# InterfacePagamentos.net
KiCad netlist of a schematic drawn in Altium Designer
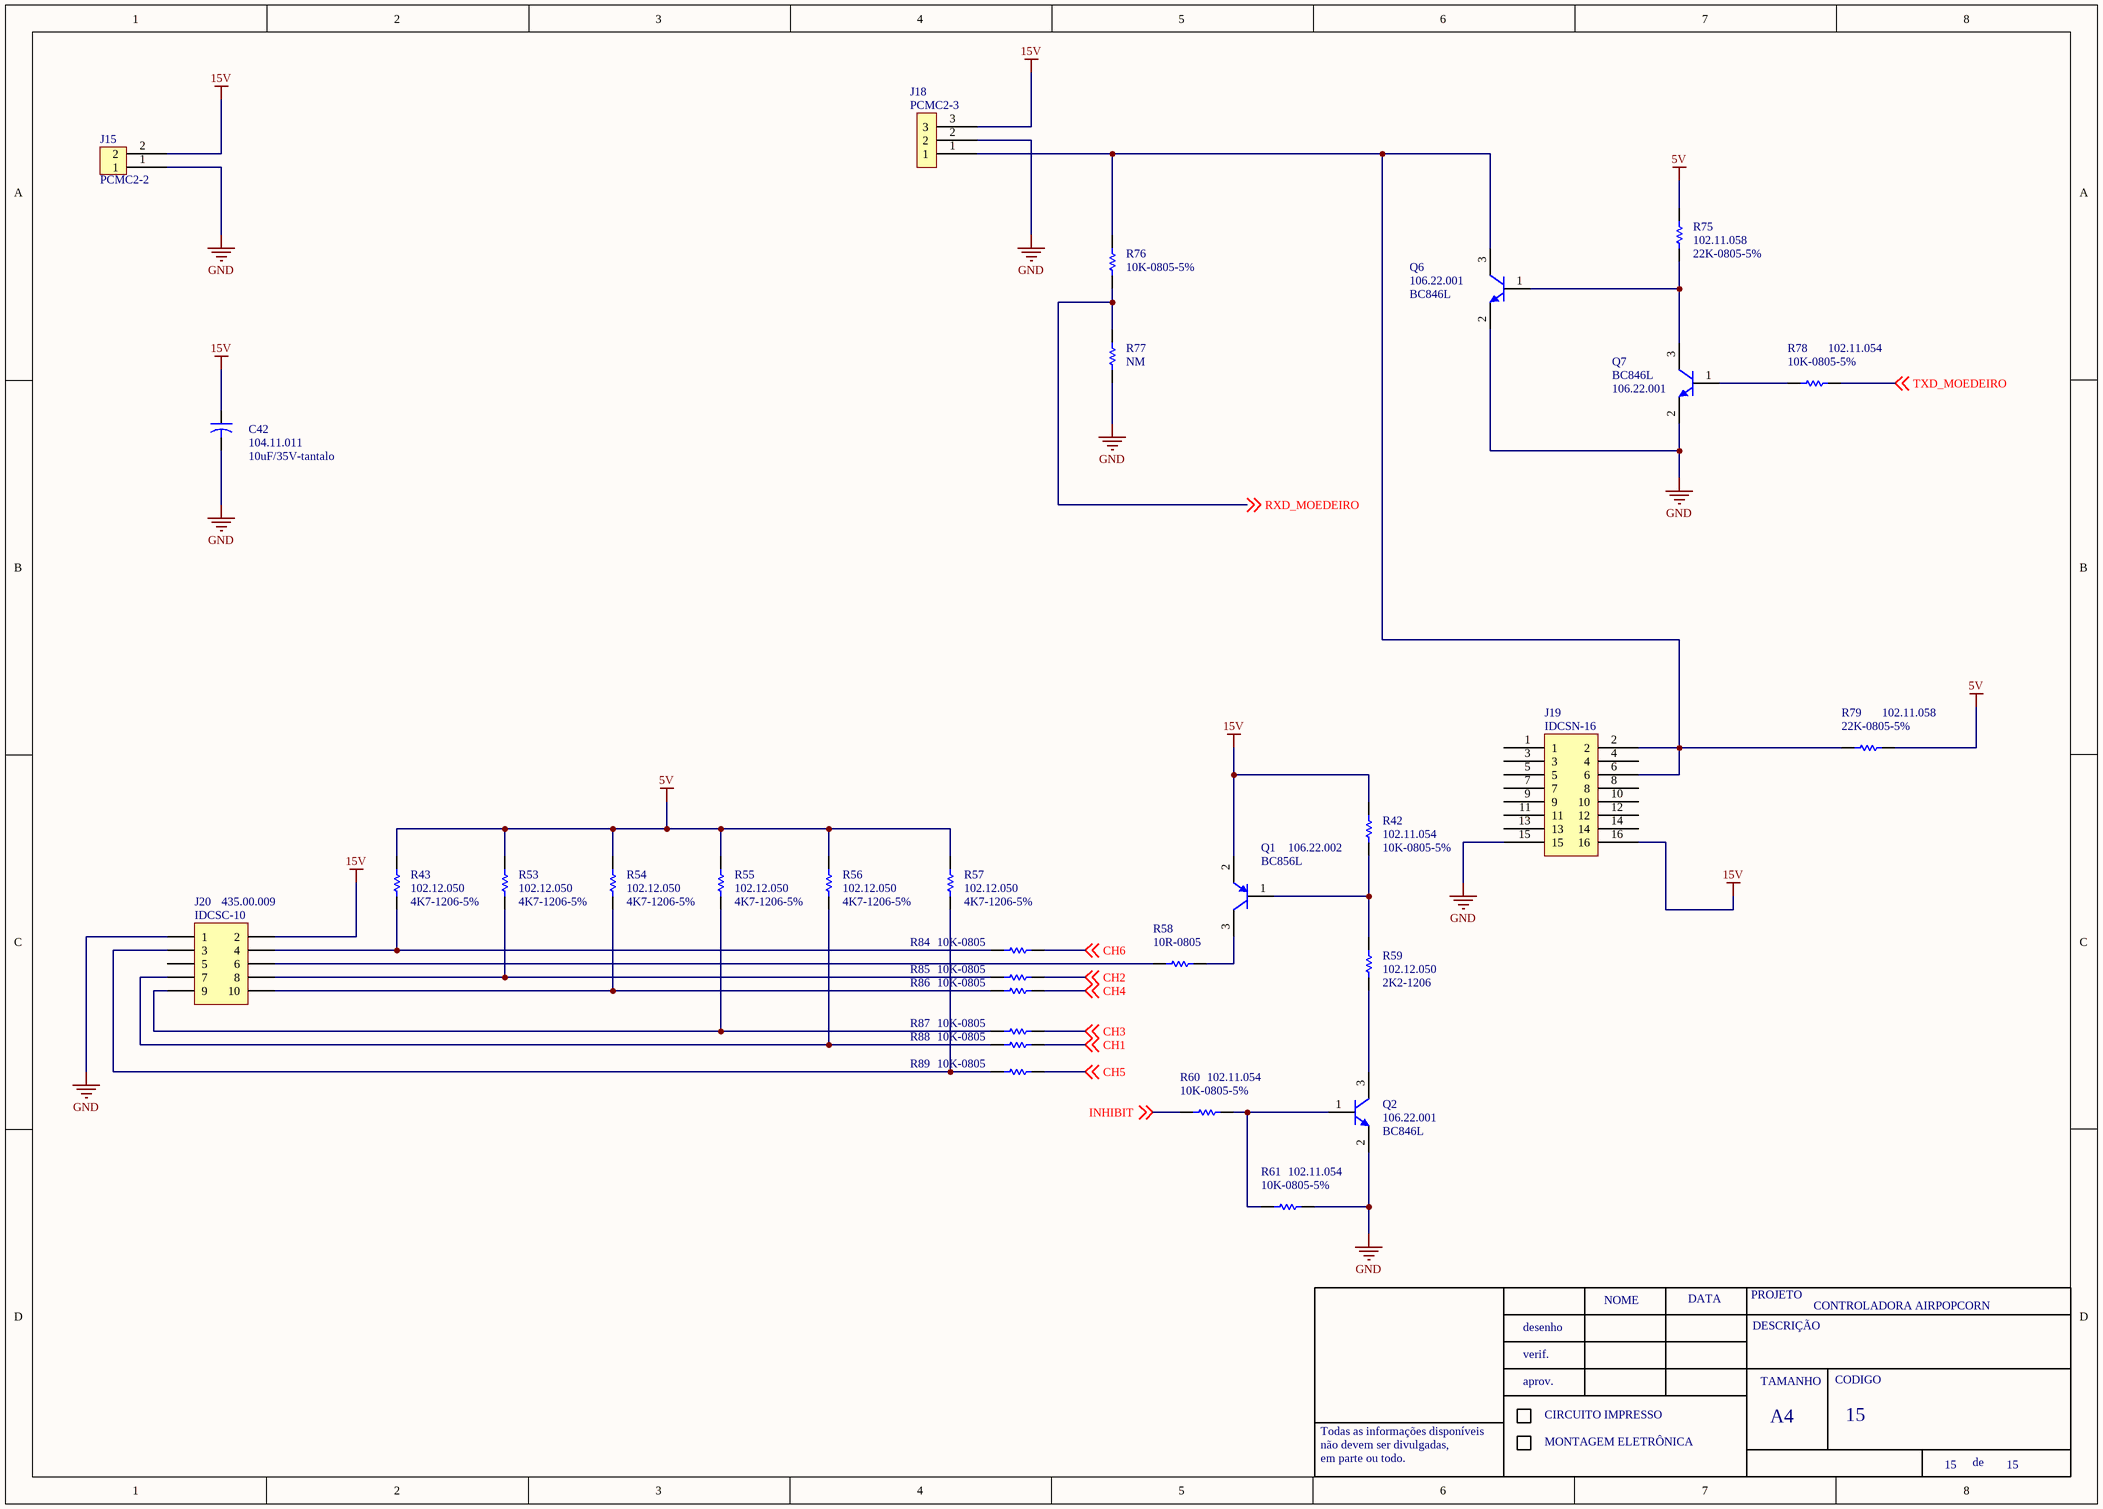
[diagram p0: InterfacePagamentos.SchDoc]

(export (version "E")
  (design (tool "Eeschema 10.0.6"))
  (components
    (comp (ref "C42")
      (value "10uF/35V-tantalo")
      (footprint "CAP 2413 POLARIZADO KEMET")
      (fields (field (name "ERP") "104.11.011"))
      (libsource (lib "AquinoLib") (part "10uF/35V-tantalo"))
    )
    (comp (ref "J15") (value "PCMC2-2") (footprint "PCMC2-2") (libsource (lib "AquinoLib") (part "PCMC2-2")))
    (comp (ref "J18") (value "PCMC2-3") (footprint "PCMC2-3") (libsource (lib "AquinoLib") (part "PCMC2-3")))
    (comp (ref "J19")
      (value "IDCSN-16")
      (footprint "IDCSC-16")
      (libsource (lib "AquinoLib") (part "IDCSN-16"))
    )
    (comp (ref "J20")
      (value "IDCSC-10")
      (footprint "IDCSC-10")
      (description "CONECTOR HEADER 10 VIAS 90º")
      (fields (field (name "ERP") "435.00.009"))
      (libsource (lib "ChaveDigital3") (part "IDCSN"))
    )
    (comp (ref "Q1")
      (value "BC856L")
      (footprint "SOT23 - REVISADO ONDA")
      (fields (field (name "ERP") "106.22.002"))
      (libsource (lib "AquinoLib") (part "BC856L"))
    )
    (comp (ref "Q2")
      (value "BC846L")
      (footprint "SOT23 - REVISADO ONDA")
      (fields (field (name "ERP") "106.22.001"))
      (libsource (lib "AquinoLib") (part "BC846"))
    )
    (comp (ref "Q6")
      (value "BC846L")
      (footprint "SOT23 - REVISADO ONDA")
      (fields (field (name "ERP") "106.22.001"))
      (libsource (lib "AquinoLib") (part "BC846"))
    )
    (comp (ref "Q7")
      (value "BC846L")
      (footprint "SOT23 - REVISADO ONDA")
      (fields (field (name "ERP") "106.22.001"))
      (libsource (lib "AquinoLib") (part "BC846"))
    )
    (comp (ref "R42")
      (value "10K-0805-5%")
      (footprint "0805-REVISADO ONDA")
      (fields (field (name "ERP") "102.11.054"))
      (libsource (lib "AquinoLib") (part "10K-0805-5%"))
    )
    (comp (ref "R43")
      (value "4K7-1206-5%")
      (footprint "0805-REVISADO ONDA")
      (fields (field (name "ERP") "102.12.050"))
      (libsource (lib "AquinoLib") (part "4K7-1206-5%"))
    )
    (comp (ref "R53")
      (value "4K7-1206-5%")
      (footprint "0805-REVISADO ONDA")
      (fields (field (name "ERP") "102.12.050"))
      (libsource (lib "AquinoLib") (part "4K7-1206-5%"))
    )
    (comp (ref "R54")
      (value "4K7-1206-5%")
      (footprint "0805-REVISADO ONDA")
      (fields (field (name "ERP") "102.12.050"))
      (libsource (lib "AquinoLib") (part "4K7-1206-5%"))
    )
    (comp (ref "R55")
      (value "4K7-1206-5%")
      (footprint "0805-REVISADO ONDA")
      (fields (field (name "ERP") "102.12.050"))
      (libsource (lib "AquinoLib") (part "4K7-1206-5%"))
    )
    (comp (ref "R56")
      (value "4K7-1206-5%")
      (footprint "0805-REVISADO ONDA")
      (fields (field (name "ERP") "102.12.050"))
      (libsource (lib "AquinoLib") (part "4K7-1206-5%"))
    )
    (comp (ref "R57")
      (value "4K7-1206-5%")
      (footprint "0805-REVISADO ONDA")
      (fields (field (name "ERP") "102.12.050"))
      (libsource (lib "AquinoLib") (part "4K7-1206-5%"))
    )
    (comp (ref "R58")
      (value "10R-0805")
      (footprint "1206-REVISADO ONDA")
      (description "10K-0805-5%")
      (libsource (lib "AquinoLib") (part "10K-0805-5%"))
    )
    (comp (ref "R59")
      (value "2K2-1206")
      (footprint "0805-REVISADO ONDA")
      (description "4K7-1206-5%")
      (fields (field (name "ERP") "102.12.050"))
      (libsource (lib "AquinoLib") (part "4K7-1206-5%"))
    )
    (comp (ref "R60")
      (value "10K-0805-5%")
      (footprint "0805-REVISADO ONDA")
      (fields (field (name "ERP") "102.11.054"))
      (libsource (lib "AquinoLib") (part "10K-0805-5%"))
    )
    (comp (ref "R61")
      (value "10K-0805-5%")
      (footprint "0805-REVISADO ONDA")
      (fields (field (name "ERP") "102.11.054"))
      (libsource (lib "AquinoLib") (part "10K-0805-5%"))
    )
    (comp (ref "R75")
      (value "22K-0805-5%")
      (footprint "0805-REVISADO ONDA")
      (fields (field (name "ERP") "102.11.058"))
      (libsource (lib "AquinoLib") (part "22K-0805-5%"))
    )
    (comp (ref "R76")
      (value "10K-0805-5%")
      (footprint "0805-REVISADO ONDA")
      (description "56K-0805-5%")
      (libsource (lib "AquinoLib") (part "56K-0805-5%"))
    )
    (comp (ref "R77")
      (value "NM")
      (footprint "0805-REVISADO ONDA")
      (description "100K-0805-5%")
      (libsource (lib "AquinoLib") (part "100K-0805-5%"))
    )
    (comp (ref "R78")
      (value "10K-0805-5%")
      (footprint "0805-REVISADO ONDA")
      (fields (field (name "ERP") "102.11.054"))
      (libsource (lib "AquinoLib") (part "10K-0805-5%"))
    )
    (comp (ref "R79")
      (value "22K-0805-5%")
      (footprint "0805-REVISADO ONDA")
      (fields (field (name "ERP") "102.11.058"))
      (libsource (lib "AquinoLib") (part "22K-0805-5%"))
    )
    (comp (ref "R84")
      (value "10K-0805")
      (footprint "1206-REVISADO ONDA")
      (description "10K-0805-5%")
      (libsource (lib "AquinoLib") (part "10K-0805-5%"))
    )
    (comp (ref "R85")
      (value "10K-0805")
      (footprint "1206-REVISADO ONDA")
      (description "10K-0805-5%")
      (libsource (lib "AquinoLib") (part "10K-0805-5%"))
    )
    (comp (ref "R86")
      (value "10K-0805")
      (footprint "1206-REVISADO ONDA")
      (description "10K-0805-5%")
      (libsource (lib "AquinoLib") (part "10K-0805-5%"))
    )
    (comp (ref "R87")
      (value "10K-0805")
      (footprint "1206-REVISADO ONDA")
      (description "10K-0805-5%")
      (libsource (lib "AquinoLib") (part "10K-0805-5%"))
    )
    (comp (ref "R88")
      (value "10K-0805")
      (footprint "1206-REVISADO ONDA")
      (description "10K-0805-5%")
      (libsource (lib "AquinoLib") (part "10K-0805-5%"))
    )
    (comp (ref "R89")
      (value "10K-0805")
      (footprint "1206-REVISADO ONDA")
      (description "10K-0805-5%")
      (libsource (lib "AquinoLib") (part "10K-0805-5%"))
    )
  )
  (nets
    (net (code "1") (name "5V") (class "Default")
      (node (ref "R43") (pin "2") (pinfunction "2_2") (pintype "passive"))
      (node (ref "R53") (pin "2") (pinfunction "2_2") (pintype "passive"))
      (node (ref "R54") (pin "2") (pinfunction "2_2") (pintype "passive"))
      (node (ref "R55") (pin "2") (pinfunction "2_2") (pintype "passive"))
      (node (ref "R56") (pin "2") (pinfunction "2_2") (pintype "passive"))
      (node (ref "R57") (pin "2") (pinfunction "2_2") (pintype "passive"))
      (node (ref "R75") (pin "2") (pinfunction "2_2") (pintype "passive"))
      (node (ref "R79") (pin "2") (pinfunction "2_2") (pintype "passive"))
    )
    (net (code "2") (name "15V") (class "Default")
      (node (ref "C42") (pin "1") (pinfunction "1_1") (pintype "passive"))
      (node (ref "J15") (pin "2") (pinfunction "2_2") (pintype "passive"))
      (node (ref "J18") (pin "3") (pinfunction "3_3") (pintype "passive"))
      (node (ref "J19") (pin "16") (pinfunction "16_16") (pintype "passive"))
      (node (ref "J20") (pin "2") (pinfunction "2_2") (pintype "passive"))
      (node (ref "Q1") (pin "2") (pinfunction "E_2") (pintype "passive"))
      (node (ref "R42") (pin "2") (pinfunction "2_2") (pintype "passive"))
    )
    (net (code "3") (name "CH1") (class "Default")
      (node (ref "R88") (pin "1") (pinfunction "1_1") (pintype "passive"))
    )
    (net (code "4") (name "CH2") (class "Default")
      (node (ref "R85") (pin "1") (pinfunction "1_1") (pintype "passive"))
    )
    (net (code "5") (name "CH3") (class "Default")
      (node (ref "R87") (pin "1") (pinfunction "1_1") (pintype "passive"))
    )
    (net (code "6") (name "CH4") (class "Default")
      (node (ref "R86") (pin "1") (pinfunction "1_1") (pintype "passive"))
    )
    (net (code "7") (name "CH5") (class "Default")
      (node (ref "R89") (pin "1") (pinfunction "1_1") (pintype "passive"))
    )
    (net (code "8") (name "CH6") (class "Default")
      (node (ref "R84") (pin "1") (pinfunction "1_1") (pintype "passive"))
    )
    (net (code "9") (name "GND") (class "Default")
      (node (ref "C42") (pin "2") (pinfunction "2_2") (pintype "passive"))
      (node (ref "J15") (pin "1") (pinfunction "1_1") (pintype "passive"))
      (node (ref "J18") (pin "2") (pinfunction "2_2") (pintype "passive"))
      (node (ref "J19") (pin "15") (pinfunction "15_15") (pintype "passive"))
      (node (ref "J20") (pin "1") (pinfunction "1_1") (pintype "passive"))
      (node (ref "Q2") (pin "2") (pinfunction "E_2") (pintype "passive"))
      (node (ref "Q6") (pin "2") (pinfunction "E_2") (pintype "passive"))
      (node (ref "Q7") (pin "2") (pinfunction "E_2") (pintype "passive"))
      (node (ref "R61") (pin "2") (pinfunction "2_2") (pintype "passive"))
      (node (ref "R77") (pin "1") (pinfunction "1_1") (pintype "passive"))
    )
    (net (code "10") (name "INHIBIT") (class "Default")
      (node (ref "R60") (pin "1") (pinfunction "1_1") (pintype "passive"))
    )
    (net (code "11") (name "Net-(J20-Pad3)") (class "Default")
      (node (ref "J20") (pin "3") (pinfunction "3_3") (pintype "passive"))
      (node (ref "R57") (pin "1") (pinfunction "1_1") (pintype "passive"))
      (node (ref "R89") (pin "2") (pinfunction "2_2") (pintype "passive"))
    )
    (net (code "12") (name "Net-(J20-Pad4)") (class "Default")
      (node (ref "J20") (pin "4") (pinfunction "4_4") (pintype "passive"))
      (node (ref "R43") (pin "1") (pinfunction "1_1") (pintype "passive"))
      (node (ref "R84") (pin "2") (pinfunction "2_2") (pintype "passive"))
    )
    (net (code "13") (name "Net-(J20-Pad6)") (class "Default")
      (node (ref "J20") (pin "6") (pinfunction "6_6") (pintype "passive"))
      (node (ref "R58") (pin "2") (pinfunction "2_2") (pintype "passive"))
    )
    (net (code "14") (name "Net-(J20-Pad7)") (class "Default")
      (node (ref "J20") (pin "7") (pinfunction "7_7") (pintype "passive"))
      (node (ref "R56") (pin "1") (pinfunction "1_1") (pintype "passive"))
      (node (ref "R88") (pin "2") (pinfunction "2_2") (pintype "passive"))
    )
    (net (code "15") (name "Net-(J20-Pad8)") (class "Default")
      (node (ref "J20") (pin "8") (pinfunction "8_8") (pintype "passive"))
      (node (ref "R53") (pin "1") (pinfunction "1_1") (pintype "passive"))
      (node (ref "R85") (pin "2") (pinfunction "2_2") (pintype "passive"))
    )
    (net (code "16") (name "Net-(J20-Pad9)") (class "Default")
      (node (ref "J20") (pin "9") (pinfunction "9_9") (pintype "passive"))
      (node (ref "R55") (pin "1") (pinfunction "1_1") (pintype "passive"))
      (node (ref "R87") (pin "2") (pinfunction "2_2") (pintype "passive"))
    )
    (net (code "17") (name "Net-(J20-Pad10)") (class "Default")
      (node (ref "J20") (pin "10") (pinfunction "10_10") (pintype "passive"))
      (node (ref "R54") (pin "1") (pinfunction "1_1") (pintype "passive"))
      (node (ref "R86") (pin "2") (pinfunction "2_2") (pintype "passive"))
    )
    (net (code "18") (name "Net-(Q1-B)") (class "Default")
      (node (ref "Q1") (pin "1") (pinfunction "B_1") (pintype "passive"))
      (node (ref "R42") (pin "1") (pinfunction "1_1") (pintype "passive"))
      (node (ref "R59") (pin "2") (pinfunction "2_2") (pintype "passive"))
    )
    (net (code "19") (name "Net-(Q1-C)") (class "Default")
      (node (ref "Q1") (pin "3") (pinfunction "C_3") (pintype "passive"))
      (node (ref "R58") (pin "1") (pinfunction "1_1") (pintype "passive"))
    )
    (net (code "20") (name "Net-(Q2-B)") (class "Default")
      (node (ref "Q2") (pin "1") (pinfunction "B_1") (pintype "passive"))
      (node (ref "R60") (pin "2") (pinfunction "2_2") (pintype "passive"))
      (node (ref "R61") (pin "1") (pinfunction "1_1") (pintype "passive"))
    )
    (net (code "21") (name "Net-(Q2-C)") (class "Default")
      (node (ref "Q2") (pin "3") (pinfunction "C_3") (pintype "passive"))
      (node (ref "R59") (pin "1") (pinfunction "1_1") (pintype "passive"))
    )
    (net (code "22") (name "Net-(Q6-B)") (class "Default")
      (node (ref "Q6") (pin "1") (pinfunction "B_1") (pintype "passive"))
      (node (ref "Q7") (pin "3") (pinfunction "C_3") (pintype "passive"))
      (node (ref "R75") (pin "1") (pinfunction "1_1") (pintype "passive"))
    )
    (net (code "23") (name "Net-(Q6-C)") (class "Default")
      (node (ref "J18") (pin "1") (pinfunction "1_1") (pintype "passive"))
      (node (ref "J19") (pin "2") (pinfunction "2_2") (pintype "passive"))
      (node (ref "J19") (pin "6") (pinfunction "6_6") (pintype "passive"))
      (node (ref "Q6") (pin "3") (pinfunction "C_3") (pintype "passive"))
      (node (ref "R76") (pin "1") (pinfunction "1_1") (pintype "passive"))
      (node (ref "R79") (pin "1") (pinfunction "1_1") (pintype "passive"))
    )
    (net (code "24") (name "Net-(Q7-B)") (class "Default")
      (node (ref "Q7") (pin "1") (pinfunction "B_1") (pintype "passive"))
      (node (ref "R78") (pin "1") (pinfunction "1_1") (pintype "passive"))
    )
    (net (code "25") (name "RXD_MOEDEIRO") (class "Default")
      (node (ref "R76") (pin "2") (pinfunction "2_2") (pintype "passive"))
      (node (ref "R77") (pin "2") (pinfunction "2_2") (pintype "passive"))
    )
    (net (code "26") (name "TXD_MOEDEIRO") (class "Default")
      (node (ref "R78") (pin "2") (pinfunction "2_2") (pintype "passive"))
    )
    (net (code "27") (name "unconnected-(J19-Pad1)") (class "Default")
      (node (ref "J19") (pin "1") (pinfunction "1_1") (pintype "passive"))
    )
    (net (code "28") (name "unconnected-(J19-Pad3)") (class "Default")
      (node (ref "J19") (pin "3") (pinfunction "3_3") (pintype "passive"))
    )
    (net (code "29") (name "unconnected-(J19-Pad4)") (class "Default")
      (node (ref "J19") (pin "4") (pinfunction "4_4") (pintype "passive"))
    )
    (net (code "30") (name "unconnected-(J19-Pad5)") (class "Default")
      (node (ref "J19") (pin "5") (pinfunction "5_5") (pintype "passive"))
    )
    (net (code "31") (name "unconnected-(J19-Pad7)") (class "Default")
      (node (ref "J19") (pin "7") (pinfunction "7_7") (pintype "passive"))
    )
    (net (code "32") (name "unconnected-(J19-Pad8)") (class "Default")
      (node (ref "J19") (pin "8") (pinfunction "8_8") (pintype "passive"))
    )
    (net (code "33") (name "unconnected-(J19-Pad9)") (class "Default")
      (node (ref "J19") (pin "9") (pinfunction "9_9") (pintype "passive"))
    )
    (net (code "34") (name "unconnected-(J19-Pad10)") (class "Default")
      (node (ref "J19") (pin "10") (pinfunction "10_10") (pintype "passive"))
    )
    (net (code "35") (name "unconnected-(J19-Pad11)") (class "Default")
      (node (ref "J19") (pin "11") (pinfunction "11_11") (pintype "passive"))
    )
    (net (code "36") (name "unconnected-(J19-Pad12)") (class "Default")
      (node (ref "J19") (pin "12") (pinfunction "12_12") (pintype "passive"))
    )
    (net (code "37") (name "unconnected-(J19-Pad13)") (class "Default")
      (node (ref "J19") (pin "13") (pinfunction "13_13") (pintype "passive"))
    )
    (net (code "38") (name "unconnected-(J19-Pad14)") (class "Default")
      (node (ref "J19") (pin "14") (pinfunction "14_14") (pintype "passive"))
    )
    (net (code "39") (name "unconnected-(J20-Pad5)") (class "Default")
      (node (ref "J20") (pin "5") (pinfunction "5_5") (pintype "passive"))
    )
  )
)
